# Coplanar_Capacitive_Sensor.net
KiCad netlist of a schematic drawn in Altium Designer
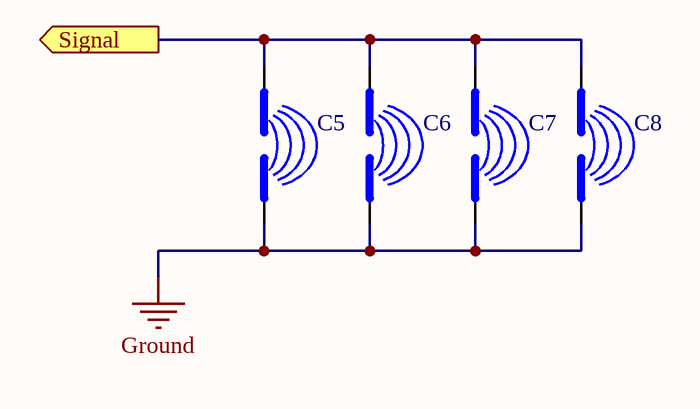
[diagram p0: Coplanar Capacitive Sensor.SchDoc]

(export (version "E")
  (design (tool "Eeschema 10.0.6"))
  (components
    (comp (ref "C5")
      (value "Coplanar Capacitor")
      (footprint "Coplanar Capacitor")
      (libsource (lib "Personal Library") (part "Coplanar Capacitor"))
    )
    (comp (ref "C6")
      (value "Coplanar Capacitor")
      (footprint "Coplanar Capacitor")
      (libsource (lib "Personal Library") (part "Coplanar Capacitor"))
    )
    (comp (ref "C7")
      (value "Coplanar Capacitor")
      (footprint "Coplanar Capacitor")
      (libsource (lib "Personal Library") (part "Coplanar Capacitor"))
    )
    (comp (ref "C8")
      (value "Coplanar Capacitor")
      (footprint "Coplanar Capacitor")
      (libsource (lib "Personal Library") (part "Coplanar Capacitor"))
    )
  )
  (nets
    (net (code "1") (name "/Signal") (class "Default")
      (node (ref "C5") (pin "2") (pinfunction "2_2") (pintype "passive"))
      (node (ref "C6") (pin "2") (pinfunction "2_2") (pintype "passive"))
      (node (ref "C7") (pin "2") (pinfunction "2_2") (pintype "passive"))
      (node (ref "C8") (pin "2") (pinfunction "2_2") (pintype "passive"))
    )
    (net (code "2") (name "Ground") (class "Default")
      (node (ref "C5") (pin "1") (pinfunction "1_1") (pintype "passive"))
      (node (ref "C6") (pin "1") (pinfunction "1_1") (pintype "passive"))
      (node (ref "C7") (pin "1") (pinfunction "1_1") (pintype "passive"))
      (node (ref "C8") (pin "1") (pinfunction "1_1") (pintype "passive"))
    )
  )
)
